# openmv-ble.net
KiCad netlist of a schematic drawn in EAGLE
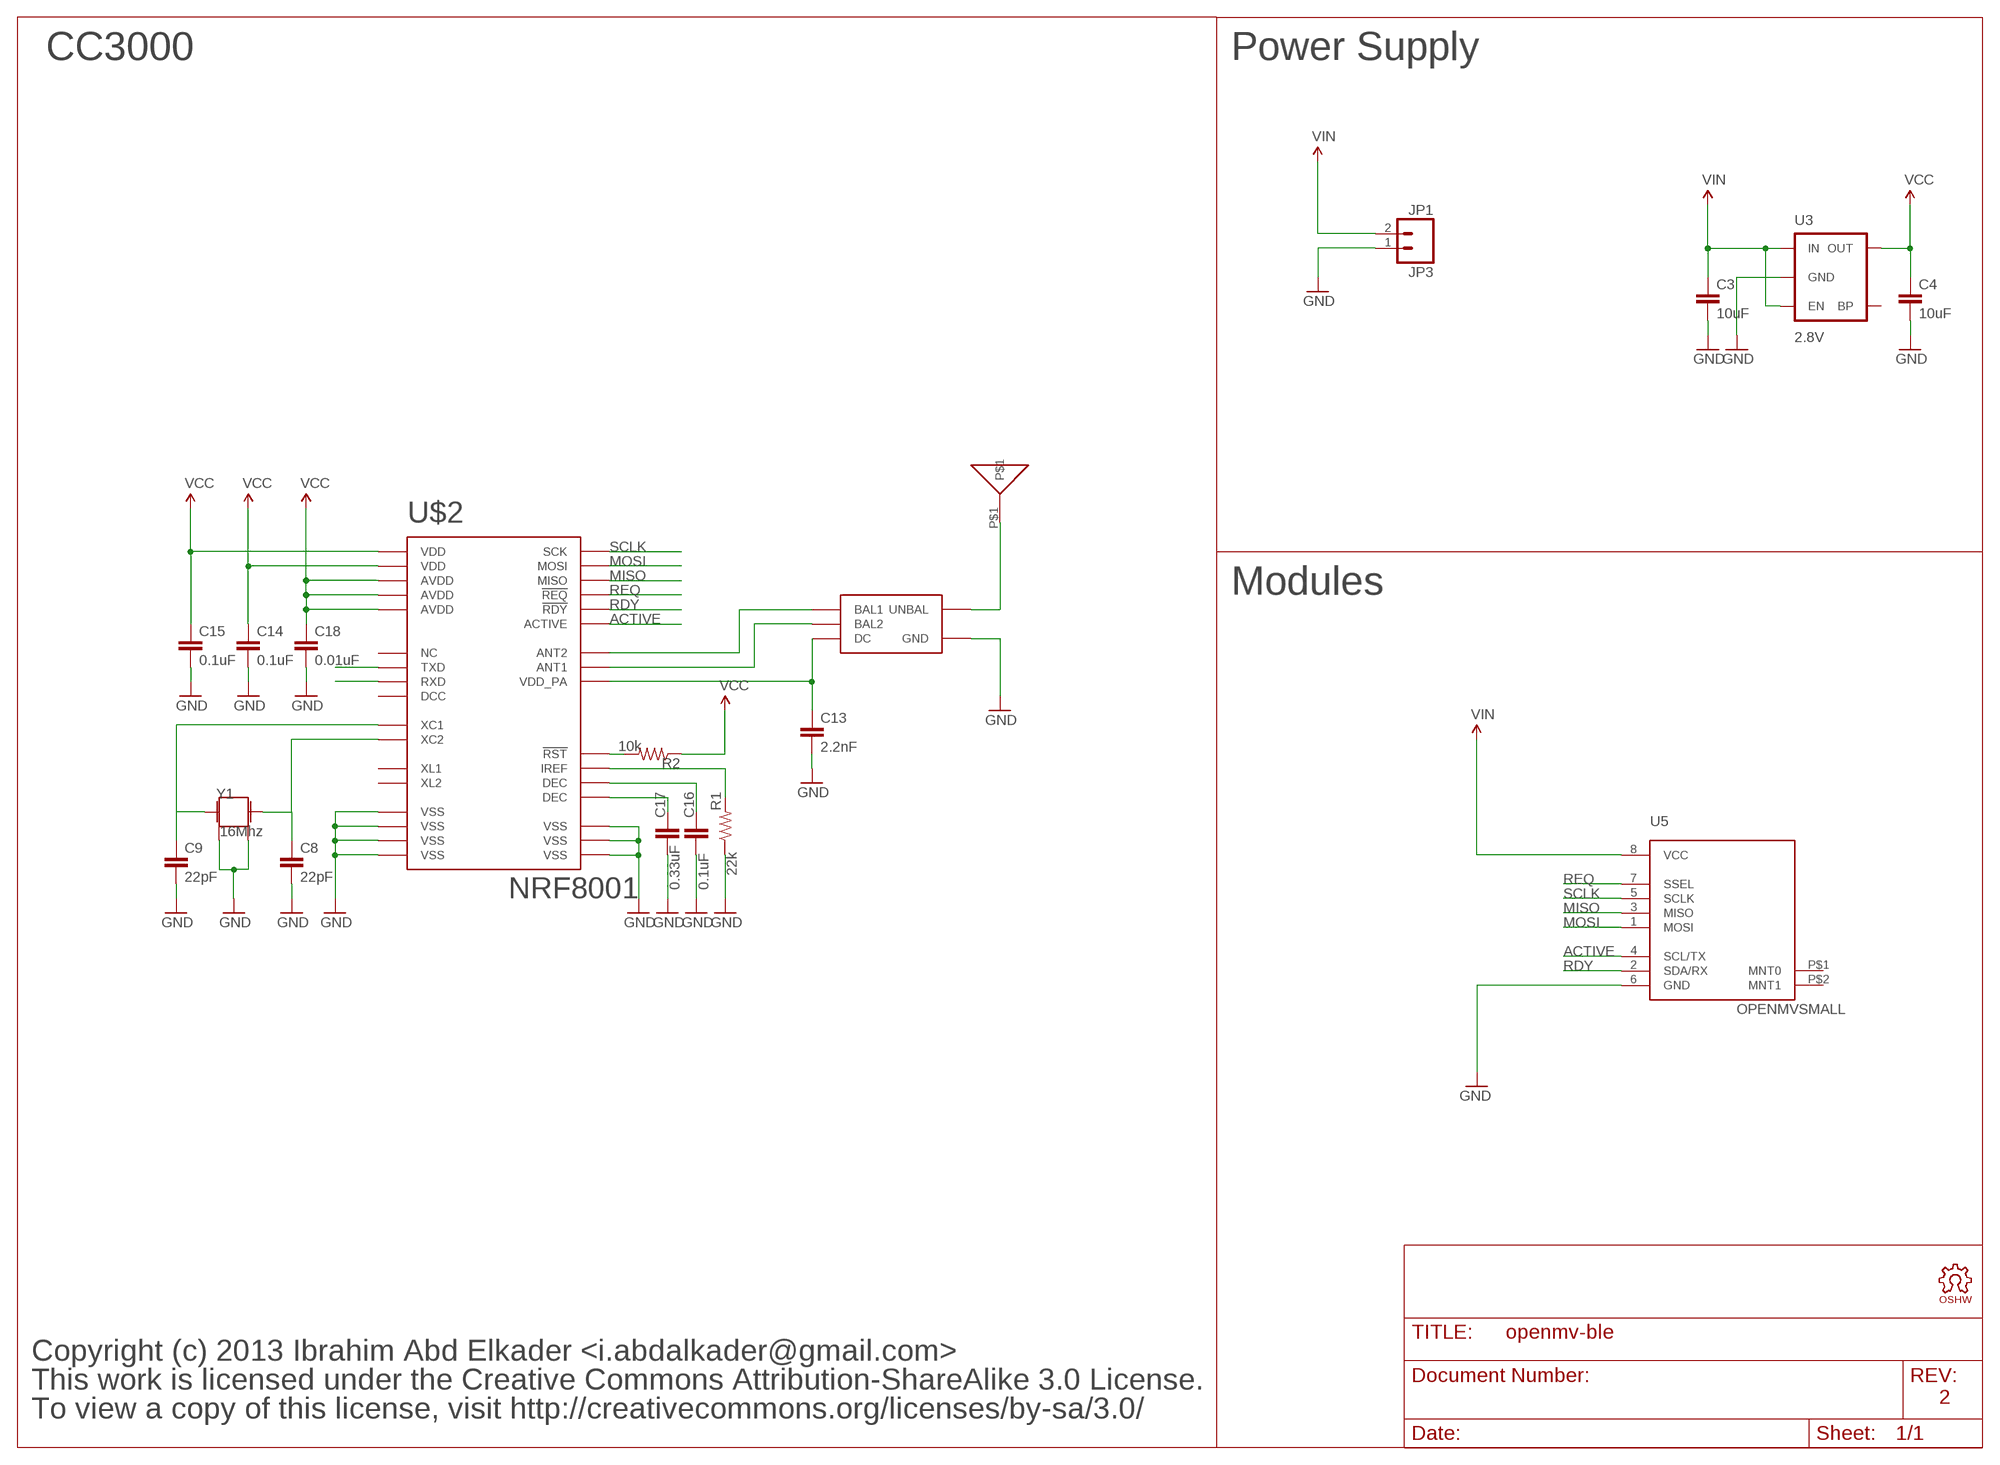
[diagram p0: schematic, sheet 1]

(export (version "E")
  (design (tool "Eeschema 10.0.6"))
  (components
    (comp (ref "C3")
      (value "10uF")
      (footprint "eagle-import:0805")
      (libsource (lib "eagle-import") (part "CAP0805"))
    )
    (comp (ref "C4")
      (value "10uF")
      (footprint "eagle-import:0805")
      (libsource (lib "eagle-import") (part "CAP0805"))
    )
    (comp (ref "C8")
      (value "22pF")
      (footprint "eagle-import:0402-CAP")
      (libsource (lib "eagle-import") (part "CAP0402-CAP"))
    )
    (comp (ref "C9")
      (value "22pF")
      (footprint "eagle-import:0402-CAP")
      (libsource (lib "eagle-import") (part "CAP0402-CAP"))
    )
    (comp (ref "C13")
      (value "2.2nF")
      (footprint "eagle-import:0402-CAP")
      (libsource (lib "eagle-import") (part "CAP0402-CAP"))
    )
    (comp (ref "C14")
      (value "0.1uF")
      (footprint "eagle-import:0402-CAP")
      (libsource (lib "eagle-import") (part "CAP0402-CAP"))
    )
    (comp (ref "C15")
      (value "0.1uF")
      (footprint "eagle-import:0402-CAP")
      (libsource (lib "eagle-import") (part "CAP0402-CAP"))
    )
    (comp (ref "C16")
      (value "0.1uF")
      (footprint "eagle-import:0402-CAP")
      (libsource (lib "eagle-import") (part "CAP0402-CAP"))
    )
    (comp (ref "C17")
      (value "0.33uF")
      (footprint "eagle-import:0402-CAP")
      (libsource (lib "eagle-import") (part "CAP0402-CAP"))
    )
    (comp (ref "C18")
      (value "0.01uF")
      (footprint "eagle-import:0402-CAP")
      (libsource (lib "eagle-import") (part "CAP0402-CAP"))
    )
    (comp (ref "JP1")
      (value "JP3")
      (footprint "eagle-import:JST-2-PTH")
      (libsource (lib "eagle-import") (part "M02JST-PTH-2"))
    )
    (comp (ref "LOGO1")
      (value "OSHW_LOGO_FILLX0100-NT")
      (footprint "eagle-import:OSHW_FILLX100_NOTEXT")
      (libsource (lib "eagle-import") (part "OSHW_LOGO_FILLX0100-NT"))
    )
    (comp (ref "R1")
      (value "22k")
      (footprint "eagle-import:0402-RES")
      (libsource (lib "eagle-import") (part "RESISTOR0402-RES"))
    )
    (comp (ref "R2")
      (value "10k")
      (footprint "eagle-import:0402-RES")
      (libsource (lib "eagle-import") (part "RESISTOR0402-RES"))
    )
    (comp (ref "U$2")
      (value "NRF8001")
      (footprint "eagle-import:QFN-32")
      (libsource (lib "eagle-import") (part "NRF8001"))
    )
    (comp (ref "U1")
      (value "2450BM14A0002")
      (footprint "eagle-import:2450BM14A0002")
      (libsource (lib "eagle-import") (part "2450BM14A0002"))
    )
    (comp (ref "U2")
      (value "ANT-YAGEO")
      (footprint "eagle-import:ANTENNA")
      (libsource (lib "eagle-import") (part "ANT-YAGEO"))
    )
    (comp (ref "U3")
      (value "2.8V")
      (footprint "eagle-import:SOT23-5")
      (libsource (lib "eagle-import") (part "V_REG_LDOSMD"))
    )
    (comp (ref "U5")
      (value "OPENMVSMALL")
      (footprint "eagle-import:OPENMV-SMALL")
      (libsource (lib "eagle-import") (part "OPENMVSMALL"))
    )
    (comp (ref "Y1")
      (value "16Mhz")
      (footprint "eagle-import:CRYSTAL3.2X2.5")
      (libsource (lib "eagle-import") (part "CRYSTAL3.2X2.5"))
    )
  )
  (nets
    (net (code "1") (name "/ACTIVE") (class "Default")
      (node (ref "U$2") (pin "P$6") (pinfunction "ACTIVE_P$6") (pintype "passive"))
      (node (ref "U5") (pin "4") (pinfunction "SCL/TX_4") (pintype "bidirectional"))
    )
    (net (code "2") (name "/DCC") (class "Default")
      (node (ref "U$2") (pin "P$32") (pinfunction "DCC_P$32") (pintype "power_in"))
    )
    (net (code "3") (name "/MISO") (class "Default")
      (node (ref "U$2") (pin "P$14") (pinfunction "MISO_P$14") (pintype "bidirectional"))
      (node (ref "U5") (pin "3") (pinfunction "MISO_3") (pintype "bidirectional"))
    )
    (net (code "4") (name "/MNT0") (class "Default")
      (node (ref "U5") (pin "P$1") (pinfunction "MNT0_P$1") (pintype "power_in"))
    )
    (net (code "5") (name "/MNT1") (class "Default")
      (node (ref "U5") (pin "P$2") (pinfunction "MNT1_P$2") (pintype "power_in"))
    )
    (net (code "6") (name "/MOSI") (class "Default")
      (node (ref "U$2") (pin "P$13") (pinfunction "MOSI_P$13") (pintype "bidirectional"))
      (node (ref "U5") (pin "1") (pinfunction "MOSI_1") (pintype "bidirectional"))
    )
    (net (code "7") (name "/RDY") (class "Default")
      (node (ref "U$2") (pin "P$16") (pinfunction "~{RDY}_P$16") (pintype "bidirectional"))
      (node (ref "U5") (pin "2") (pinfunction "SDA/RX_2") (pintype "bidirectional"))
    )
    (net (code "8") (name "/REQ") (class "Default")
      (node (ref "U$2") (pin "P$12") (pinfunction "~{REQ}_P$12") (pintype "bidirectional"))
      (node (ref "U5") (pin "7") (pinfunction "SSEL_7") (pintype "bidirectional"))
    )
    (net (code "9") (name "/SCLK") (class "Default")
      (node (ref "U$2") (pin "P$11") (pinfunction "SCK_P$11") (pintype "bidirectional"))
      (node (ref "U5") (pin "5") (pinfunction "SCLK_5") (pintype "bidirectional"))
    )
    (net (code "10") (name "GND") (class "Default")
      (node (ref "C13") (pin "2") (pinfunction "2_2") (pintype "passive"))
      (node (ref "C14") (pin "2") (pinfunction "2_2") (pintype "passive"))
      (node (ref "C15") (pin "2") (pinfunction "2_2") (pintype "passive"))
      (node (ref "C16") (pin "2") (pinfunction "2_2") (pintype "passive"))
      (node (ref "C17") (pin "2") (pinfunction "2_2") (pintype "passive"))
      (node (ref "C18") (pin "2") (pinfunction "2_2") (pintype "passive"))
      (node (ref "C3") (pin "2") (pinfunction "2_2") (pintype "passive"))
      (node (ref "C4") (pin "2") (pinfunction "2_2") (pintype "passive"))
      (node (ref "C8") (pin "2") (pinfunction "2_2") (pintype "passive"))
      (node (ref "C9") (pin "2") (pinfunction "2_2") (pintype "passive"))
      (node (ref "JP1") (pin "1") (pinfunction "2_1") (pintype "passive"))
      (node (ref "R1") (pin "1") (pinfunction "1_1") (pintype "passive"))
      (node (ref "U$2") (pin "P$17") (pinfunction "VSS_P$17") (pintype "power_in"))
      (node (ref "U$2") (pin "P$18") (pinfunction "VSS_P$18") (pintype "power_in"))
      (node (ref "U$2") (pin "P$23") (pinfunction "VSS_P$23") (pintype "power_in"))
      (node (ref "U$2") (pin "P$30") (pinfunction "VSS_P$30") (pintype "power_in"))
      (node (ref "U$2") (pin "P$31") (pinfunction "VSS_P$31") (pintype "power_in"))
      (node (ref "U$2") (pin "P$33") (pinfunction "VSS_P$33") (pintype "power_in"))
      (node (ref "U$2") (pin "P$8") (pinfunction "VSS_P$8") (pintype "power_in"))
      (node (ref "U1") (pin "P$2") (pinfunction "GND_P$2") (pintype "bidirectional"))
      (node (ref "U3") (pin "2") (pinfunction "GND_2") (pintype "input"))
      (node (ref "U5") (pin "6") (pinfunction "GND_6") (pintype "power_in"))
      (node (ref "Y1") (pin "2") (pinfunction "P$1_2") (pintype "power_in"))
      (node (ref "Y1") (pin "4") (pinfunction "P$2_4") (pintype "power_in"))
    )
    (net (code "11") (name "Net-(C16-Pad1)") (class "Default")
      (node (ref "C16") (pin "1") (pinfunction "1_1") (pintype "passive"))
      (node (ref "U$2") (pin "P$3") (pinfunction "DEC_P$3") (pintype "power_in"))
    )
    (net (code "12") (name "Net-(C17-Pad1)") (class "Default")
      (node (ref "C17") (pin "1") (pinfunction "1_1") (pintype "passive"))
      (node (ref "U$2") (pin "P$2") (pinfunction "DEC_P$2") (pintype "power_in"))
    )
    (net (code "13") (name "Net-(U$2-ANT1)") (class "Default")
      (node (ref "U$2") (pin "P$21") (pinfunction "ANT1_P$21") (pintype "passive"))
      (node (ref "U1") (pin "P$4") (pinfunction "BAL2_P$4") (pintype "bidirectional"))
    )
    (net (code "14") (name "Net-(U$2-ANT2)") (class "Default")
      (node (ref "U$2") (pin "P$22") (pinfunction "ANT2_P$22") (pintype "passive"))
      (node (ref "U1") (pin "P$3") (pinfunction "BAL1_P$3") (pintype "bidirectional"))
    )
    (net (code "15") (name "Net-(U$2-IREF)") (class "Default")
      (node (ref "R1") (pin "2") (pinfunction "2_2") (pintype "passive"))
      (node (ref "U$2") (pin "P$25") (pinfunction "IREF_P$25") (pintype "power_in"))
    )
    (net (code "16") (name "Net-(U$2-VDD_PA)") (class "Default")
      (node (ref "C13") (pin "1") (pinfunction "1_1") (pintype "passive"))
      (node (ref "U$2") (pin "P$20") (pinfunction "VDD_PA_P$20") (pintype "power_in"))
      (node (ref "U1") (pin "P$5") (pinfunction "DC_P$5") (pintype "bidirectional"))
    )
    (net (code "17") (name "Net-(U$2-XC1)") (class "Default")
      (node (ref "C9") (pin "1") (pinfunction "1_1") (pintype "passive"))
      (node (ref "U$2") (pin "P$28") (pinfunction "XC1_P$28") (pintype "passive"))
      (node (ref "Y1") (pin "3") (pinfunction "2_3") (pintype "passive"))
    )
    (net (code "18") (name "Net-(U$2-XC2)") (class "Default")
      (node (ref "C8") (pin "1") (pinfunction "1_1") (pintype "passive"))
      (node (ref "U$2") (pin "P$27") (pinfunction "XC2_P$27") (pintype "passive"))
      (node (ref "Y1") (pin "1") (pinfunction "1_1") (pintype "passive"))
    )
    (net (code "19") (name "Net-(U$2-~{RST})") (class "Default")
      (node (ref "R2") (pin "2") (pinfunction "2_2") (pintype "passive"))
      (node (ref "U$2") (pin "P$19") (pinfunction "~{RST}_P$19") (pintype "bidirectional"))
    )
    (net (code "20") (name "Net-(U1-UNBAL)") (class "Default")
      (node (ref "U1") (pin "P$1") (pinfunction "UNBAL_P$1") (pintype "bidirectional"))
      (node (ref "U2") (pin "P$1") (pinfunction "P$1_P$1") (pintype "bidirectional"))
    )
    (net (code "21") (name "VCC") (class "Default")
      (node (ref "C14") (pin "1") (pinfunction "1_1") (pintype "passive"))
      (node (ref "C15") (pin "1") (pinfunction "1_1") (pintype "passive"))
      (node (ref "C18") (pin "1") (pinfunction "1_1") (pintype "passive"))
      (node (ref "C4") (pin "1") (pinfunction "1_1") (pintype "passive"))
      (node (ref "R2") (pin "1") (pinfunction "1_1") (pintype "passive"))
      (node (ref "U$2") (pin "P$1") (pinfunction "VDD_P$1") (pintype "power_in"))
      (node (ref "U$2") (pin "P$24") (pinfunction "AVDD_P$24") (pintype "power_in"))
      (node (ref "U$2") (pin "P$26") (pinfunction "AVDD_P$26") (pintype "power_in"))
      (node (ref "U$2") (pin "P$29") (pinfunction "AVDD_P$29") (pintype "power_in"))
      (node (ref "U$2") (pin "P$9") (pinfunction "VDD_P$9") (pintype "power_in"))
      (node (ref "U3") (pin "5") (pinfunction "OUT_5") (pintype "passive"))
    )
    (net (code "22") (name "VIN") (class "Default")
      (node (ref "C3") (pin "1") (pinfunction "1_1") (pintype "passive"))
      (node (ref "JP1") (pin "2") (pinfunction "1_2") (pintype "passive"))
      (node (ref "U3") (pin "1") (pinfunction "IN_1") (pintype "input"))
      (node (ref "U3") (pin "3") (pinfunction "EN_3") (pintype "input"))
      (node (ref "U5") (pin "8") (pinfunction "VCC_8") (pintype "power_in"))
    )
    (net (code "23") (name "unconnected-(U$2-NC-PadP$15)") (class "Default")
      (node (ref "U$2") (pin "P$15") (pinfunction "NC_P$15") (pintype "no_connect"))
    )
    (net (code "24") (name "unconnected-(U$2-RXD-PadP$10)") (class "Default")
      (node (ref "U$2") (pin "P$10") (pinfunction "RXD_P$10") (pintype "bidirectional"))
    )
    (net (code "25") (name "unconnected-(U$2-TXD-PadP$7)") (class "Default")
      (node (ref "U$2") (pin "P$7") (pinfunction "TXD_P$7") (pintype "bidirectional"))
    )
    (net (code "26") (name "unconnected-(U$2-XL1-PadP$5)") (class "Default")
      (node (ref "U$2") (pin "P$5") (pinfunction "XL1_P$5") (pintype "passive"))
    )
    (net (code "27") (name "unconnected-(U$2-XL2-PadP$4)") (class "Default")
      (node (ref "U$2") (pin "P$4") (pinfunction "XL2_P$4") (pintype "passive"))
    )
    (net (code "28") (name "unconnected-(U1-NC-PadP$6)") (class "Default")
      (node (ref "U1") (pin "P$6") (pinfunction "NC_P$6") (pintype "bidirectional"))
    )
    (net (code "29") (name "unconnected-(U3-BP-Pad4)") (class "Default")
      (node (ref "U3") (pin "4") (pinfunction "BP_4") (pintype "input"))
    )
  )
)
